# infinity_mirror_v0_9_0.net
KiCad netlist of a schematic drawn in EAGLE
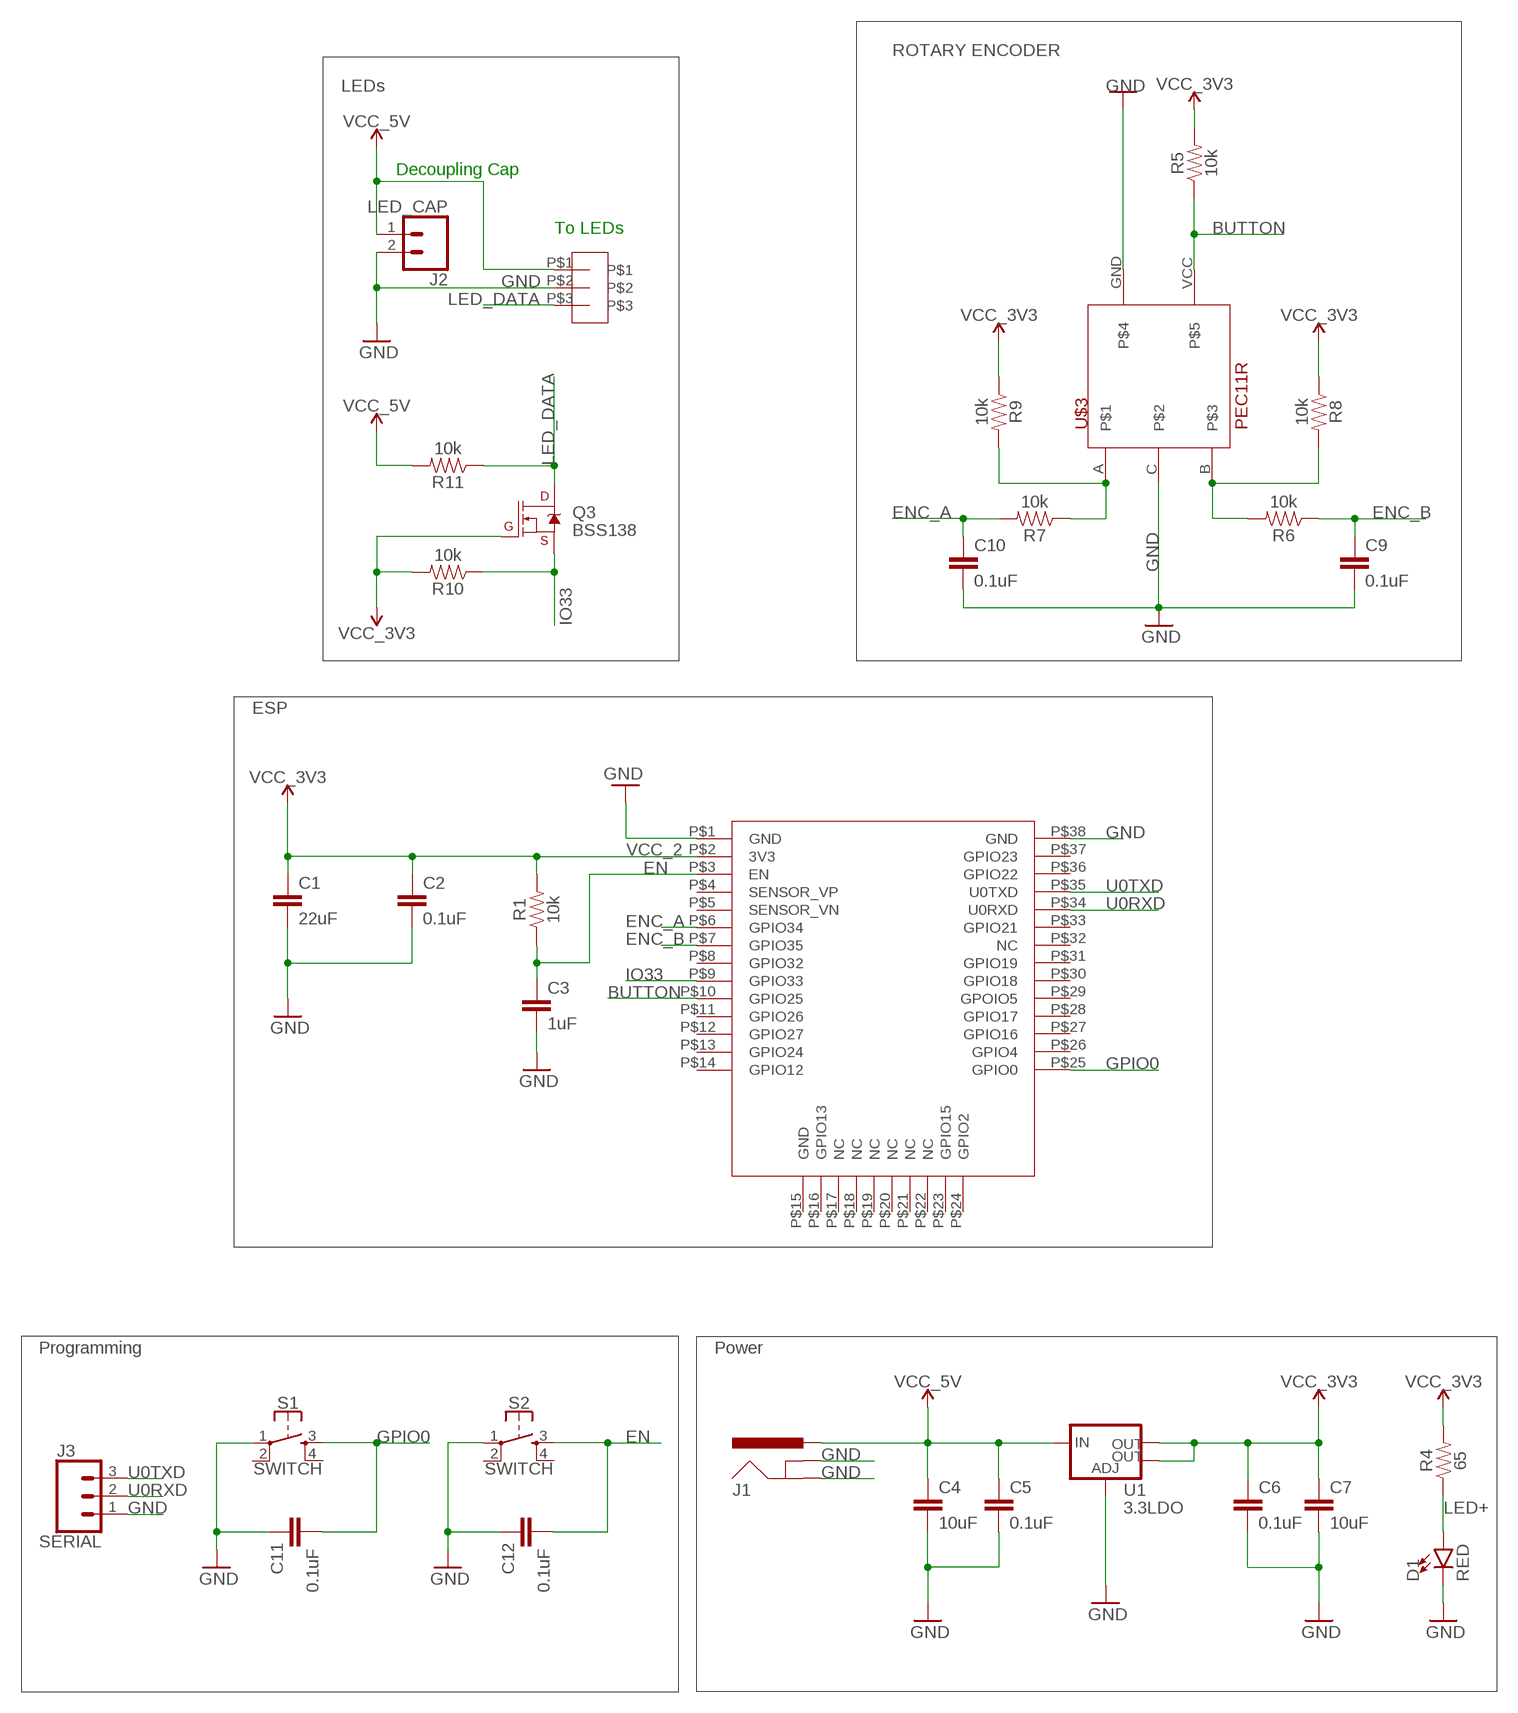
[diagram p0: schematic, sheet 1]

(export (version "E")
  (design (tool "Eeschema 10.0.6"))
  (components
    (comp (ref "C1")
      (value "22uF")
      (footprint "eagle-import:0805")
      (libsource (lib "eagle-import") (part "CAPACITOR"))
    )
    (comp (ref "C2")
      (value "0.1uF")
      (footprint "eagle-import:0805")
      (libsource (lib "eagle-import") (part "CAPACITOR"))
    )
    (comp (ref "C3")
      (value "1uF")
      (footprint "eagle-import:0805")
      (libsource (lib "eagle-import") (part "CAPACITOR"))
    )
    (comp (ref "C4")
      (value "10uF")
      (footprint "eagle-import:0805")
      (libsource (lib "eagle-import") (part "CAPACITOR"))
    )
    (comp (ref "C5")
      (value "0.1uF")
      (footprint "eagle-import:0805")
      (libsource (lib "eagle-import") (part "CAPACITOR"))
    )
    (comp (ref "C6")
      (value "0.1uF")
      (footprint "eagle-import:0805")
      (libsource (lib "eagle-import") (part "CAPACITOR"))
    )
    (comp (ref "C7")
      (value "10uF")
      (footprint "eagle-import:0805")
      (libsource (lib "eagle-import") (part "CAPACITOR"))
    )
    (comp (ref "C9")
      (value "0.1uF")
      (footprint "eagle-import:0805")
      (libsource (lib "eagle-import") (part "CAPACITOR"))
    )
    (comp (ref "C10")
      (value "0.1uF")
      (footprint "eagle-import:0805")
      (libsource (lib "eagle-import") (part "CAPACITOR"))
    )
    (comp (ref "C11")
      (value "0.1uF")
      (footprint "eagle-import:0805")
      (libsource (lib "eagle-import") (part "CAPACITOR"))
    )
    (comp (ref "C12")
      (value "0.1uF")
      (footprint "eagle-import:0805")
      (libsource (lib "eagle-import") (part "CAPACITOR"))
    )
    (comp (ref "D1")
      (value "RED")
      (footprint "eagle-import:LED-1206")
      (libsource (lib "eagle-import") (part "LED-RED1206"))
    )
    (comp (ref "J1")
      (value "POWER_JACKPTH_BREAD")
      (footprint "eagle-import:POWER_JACK_PTH_BREAD")
      (libsource (lib "eagle-import") (part "POWER_JACKPTH_BREAD"))
    )
    (comp (ref "J2")
      (value "LED_CAP")
      (footprint "eagle-import:1X02")
      (libsource (lib "eagle-import") (part "CONN_02"))
    )
    (comp (ref "J3")
      (value "SERIAL")
      (footprint "eagle-import:1X03")
      (libsource (lib "eagle-import") (part "CONN_03"))
    )
    (comp (ref "Q3")
      (value "BSS138")
      (footprint "eagle-import:SOT23-3")
      (libsource (lib "eagle-import") (part "MOSFET-NCH-BSS138"))
    )
    (comp (ref "R1")
      (value "10k")
      (footprint "eagle-import:0805")
      (libsource (lib "eagle-import") (part "RESISTOR"))
    )
    (comp (ref "R4")
      (value "65")
      (footprint "eagle-import:0805")
      (libsource (lib "eagle-import") (part "RESISTOR"))
    )
    (comp (ref "R5")
      (value "10k")
      (footprint "eagle-import:0805")
      (libsource (lib "eagle-import") (part "RESISTOR"))
    )
    (comp (ref "R6")
      (value "10k")
      (footprint "eagle-import:0805")
      (libsource (lib "eagle-import") (part "RESISTOR"))
    )
    (comp (ref "R7")
      (value "10k")
      (footprint "eagle-import:0805")
      (libsource (lib "eagle-import") (part "RESISTOR"))
    )
    (comp (ref "R8")
      (value "10k")
      (footprint "eagle-import:0805")
      (libsource (lib "eagle-import") (part "RESISTOR"))
    )
    (comp (ref "R9")
      (value "10k")
      (footprint "eagle-import:0805")
      (libsource (lib "eagle-import") (part "RESISTOR"))
    )
    (comp (ref "R10")
      (value "10k")
      (footprint "eagle-import:0805")
      (libsource (lib "eagle-import") (part "RESISTOR"))
    )
    (comp (ref "R11")
      (value "10k")
      (footprint "eagle-import:0805")
      (libsource (lib "eagle-import") (part "RESISTOR"))
    )
    (comp (ref "S1")
      (value "SWITCH")
      (footprint "eagle-import:TACTILE_SWITCH_SMD_5.2MM")
      (libsource (lib "eagle-import") (part "MOMENTARY-SWITCH-SPST-2-SMD-5.2MM-TALL"))
    )
    (comp (ref "S2")
      (value "SWITCH")
      (footprint "eagle-import:TACTILE_SWITCH_SMD_5.2MM")
      (libsource (lib "eagle-import") (part "MOMENTARY-SWITCH-SPST-2-SMD-5.2MM-TALL"))
    )
    (comp (ref "U$1")
      (value "ESP32-WROOM-32E")
      (footprint "eagle-import:ESP32-WROOM-32E")
      (libsource (lib "eagle-import") (part "ESP32-WROOM-32E"))
    )
    (comp (ref "U$2")
      (value "3-PIN-JST")
      (footprint "eagle-import:3-PIN-JST")
      (libsource (lib "eagle-import") (part "3-PIN-JST"))
    )
    (comp (ref "U$3")
      (value "PEC11R")
      (footprint "eagle-import:PEC11R-4320F-S0012")
      (libsource (lib "eagle-import") (part "PEC11R_ROTARY_ENCODER"))
    )
    (comp (ref "U1")
      (value "3.3LDO")
      (footprint "eagle-import:SOT223")
      (libsource (lib "eagle-import") (part "V_REG_LM1117SOT223"))
    )
  )
  (nets
    (net (code "1") (name "/BUTTON") (class "Default")
      (node (ref "R5") (pin "1") (pinfunction "1_1") (pintype "passive"))
      (node (ref "U$1") (pin "P$10") (pinfunction "GPIO25_P$10") (pintype "bidirectional"))
      (node (ref "U$3") (pin "VCC") (pinfunction "P$5_VCC") (pintype "bidirectional"))
    )
    (net (code "2") (name "/EN") (class "Default")
      (node (ref "C12") (pin "2") (pinfunction "2_2") (pintype "passive"))
      (node (ref "C3") (pin "1") (pinfunction "1_1") (pintype "passive"))
      (node (ref "R1") (pin "1") (pinfunction "1_1") (pintype "passive"))
      (node (ref "S2") (pin "3") (pinfunction "3_3") (pintype "passive"))
      (node (ref "U$1") (pin "P$3") (pinfunction "EN_P$3") (pintype "bidirectional"))
    )
    (net (code "3") (name "/ENC_A") (class "Default")
      (node (ref "C10") (pin "1") (pinfunction "1_1") (pintype "passive"))
      (node (ref "R7") (pin "2") (pinfunction "2_2") (pintype "passive"))
      (node (ref "U$1") (pin "P$6") (pinfunction "GPIO34_P$6") (pintype "bidirectional"))
    )
    (net (code "4") (name "/ENC_B") (class "Default")
      (node (ref "C9") (pin "1") (pinfunction "1_1") (pintype "passive"))
      (node (ref "R6") (pin "1") (pinfunction "1_1") (pintype "passive"))
      (node (ref "U$1") (pin "P$7") (pinfunction "GPIO35_P$7") (pintype "bidirectional"))
    )
    (net (code "5") (name "/GPIO0") (class "Default")
      (node (ref "C11") (pin "2") (pinfunction "2_2") (pintype "passive"))
      (node (ref "S1") (pin "3") (pinfunction "3_3") (pintype "passive"))
      (node (ref "U$1") (pin "P$25") (pinfunction "GPIO0_P$25") (pintype "bidirectional"))
    )
    (net (code "6") (name "/IO33") (class "Default")
      (node (ref "Q3") (pin "2") (pinfunction "S_2") (pintype "bidirectional"))
      (node (ref "R10") (pin "1") (pinfunction "1_1") (pintype "passive"))
      (node (ref "U$1") (pin "P$9") (pinfunction "GPIO33_P$9") (pintype "bidirectional"))
    )
    (net (code "7") (name "/LED+") (class "Default")
      (node (ref "D1") (pin "A") (pinfunction "A_A") (pintype "passive"))
      (node (ref "R4") (pin "1") (pinfunction "1_1") (pintype "passive"))
    )
    (net (code "8") (name "/LED_DATA") (class "Default")
      (node (ref "Q3") (pin "3") (pinfunction "D_3") (pintype "bidirectional"))
      (node (ref "R11") (pin "1") (pinfunction "1_1") (pintype "passive"))
      (node (ref "U$2") (pin "P$3") (pinfunction "P$3_P$3") (pintype "bidirectional"))
    )
    (net (code "9") (name "/U0RXD") (class "Default")
      (node (ref "J3") (pin "2") (pinfunction "2_2") (pintype "passive"))
      (node (ref "U$1") (pin "P$34") (pinfunction "U0RXD_P$34") (pintype "bidirectional"))
    )
    (net (code "10") (name "/U0TXD") (class "Default")
      (node (ref "J3") (pin "3") (pinfunction "3_3") (pintype "passive"))
      (node (ref "U$1") (pin "P$35") (pinfunction "U0TXD_P$35") (pintype "bidirectional"))
    )
    (net (code "11") (name "GND") (class "Default")
      (node (ref "C1") (pin "2") (pinfunction "2_2") (pintype "passive"))
      (node (ref "C10") (pin "2") (pinfunction "2_2") (pintype "passive"))
      (node (ref "C11") (pin "1") (pinfunction "1_1") (pintype "passive"))
      (node (ref "C12") (pin "1") (pinfunction "1_1") (pintype "passive"))
      (node (ref "C2") (pin "2") (pinfunction "2_2") (pintype "passive"))
      (node (ref "C3") (pin "2") (pinfunction "2_2") (pintype "passive"))
      (node (ref "C4") (pin "2") (pinfunction "2_2") (pintype "passive"))
      (node (ref "C5") (pin "2") (pinfunction "2_2") (pintype "passive"))
      (node (ref "C6") (pin "2") (pinfunction "2_2") (pintype "passive"))
      (node (ref "C7") (pin "2") (pinfunction "2_2") (pintype "passive"))
      (node (ref "C9") (pin "2") (pinfunction "2_2") (pintype "passive"))
      (node (ref "D1") (pin "C") (pinfunction "C_C") (pintype "passive"))
      (node (ref "J1") (pin "GND") (pinfunction "GND_GND") (pintype "bidirectional"))
      (node (ref "J1") (pin "GNDBREAK") (pinfunction "GNDBREAK_GNDBREAK") (pintype "bidirectional"))
      (node (ref "J2") (pin "2") (pinfunction "2_2") (pintype "passive"))
      (node (ref "J3") (pin "1") (pinfunction "1_1") (pintype "passive"))
      (node (ref "S1") (pin "1") (pinfunction "1_1") (pintype "passive"))
      (node (ref "S2") (pin "1") (pinfunction "1_1") (pintype "passive"))
      (node (ref "U$1") (pin "P$1") (pinfunction "GND_P$1") (pintype "bidirectional"))
      (node (ref "U$1") (pin "P$38") (pinfunction "GND_P$38") (pintype "bidirectional"))
      (node (ref "U$2") (pin "P$2") (pinfunction "P$2_P$2") (pintype "bidirectional"))
      (node (ref "U$3") (pin "C") (pinfunction "P$2_C") (pintype "bidirectional"))
      (node (ref "U$3") (pin "GND") (pinfunction "P$4_GND") (pintype "bidirectional"))
      (node (ref "U1") (pin "1") (pinfunction "ADJ_1") (pintype "input"))
    )
    (net (code "12") (name "Net-(U$3-P$1)") (class "Default")
      (node (ref "R7") (pin "1") (pinfunction "1_1") (pintype "passive"))
      (node (ref "R9") (pin "2") (pinfunction "2_2") (pintype "passive"))
      (node (ref "U$3") (pin "A") (pinfunction "P$1_A") (pintype "bidirectional"))
    )
    (net (code "13") (name "Net-(U$3-P$3)") (class "Default")
      (node (ref "R6") (pin "2") (pinfunction "2_2") (pintype "passive"))
      (node (ref "R8") (pin "2") (pinfunction "2_2") (pintype "passive"))
      (node (ref "U$3") (pin "B") (pinfunction "P$3_B") (pintype "bidirectional"))
    )
    (net (code "14") (name "VCC_3V3") (class "Default")
      (node (ref "C1") (pin "1") (pinfunction "1_1") (pintype "passive"))
      (node (ref "C2") (pin "1") (pinfunction "1_1") (pintype "passive"))
      (node (ref "C6") (pin "1") (pinfunction "1_1") (pintype "passive"))
      (node (ref "C7") (pin "1") (pinfunction "1_1") (pintype "passive"))
      (node (ref "Q3") (pin "1") (pinfunction "G_1") (pintype "bidirectional"))
      (node (ref "R1") (pin "2") (pinfunction "2_2") (pintype "passive"))
      (node (ref "R10") (pin "2") (pinfunction "2_2") (pintype "passive"))
      (node (ref "R4") (pin "2") (pinfunction "2_2") (pintype "passive"))
      (node (ref "R5") (pin "2") (pinfunction "2_2") (pintype "passive"))
      (node (ref "R8") (pin "1") (pinfunction "1_1") (pintype "passive"))
      (node (ref "R9") (pin "1") (pinfunction "1_1") (pintype "passive"))
      (node (ref "U$1") (pin "P$2") (pinfunction "3V3_P$2") (pintype "bidirectional"))
      (node (ref "U1") (pin "2") (pinfunction "OUT_2") (pintype "output"))
      (node (ref "U1") (pin "4") (pinfunction "OUT_4") (pintype "output"))
    )
    (net (code "15") (name "VCC_5V") (class "Default")
      (node (ref "C4") (pin "1") (pinfunction "1_1") (pintype "passive"))
      (node (ref "C5") (pin "1") (pinfunction "1_1") (pintype "passive"))
      (node (ref "J1") (pin "PWR") (pinfunction "PWR_PWR") (pintype "bidirectional"))
      (node (ref "J2") (pin "1") (pinfunction "1_1") (pintype "passive"))
      (node (ref "R11") (pin "2") (pinfunction "2_2") (pintype "passive"))
      (node (ref "U$2") (pin "P$1") (pinfunction "P$1_P$1") (pintype "bidirectional"))
      (node (ref "U1") (pin "3") (pinfunction "IN_3") (pintype "input"))
    )
    (net (code "16") (name "unconnected-(S1-Pad2)") (class "Default")
      (node (ref "S1") (pin "2") (pinfunction "2_2") (pintype "passive"))
    )
    (net (code "17") (name "unconnected-(S1-Pad4)") (class "Default")
      (node (ref "S1") (pin "4") (pinfunction "4_4") (pintype "passive"))
    )
    (net (code "18") (name "unconnected-(S2-Pad2)") (class "Default")
      (node (ref "S2") (pin "2") (pinfunction "2_2") (pintype "passive"))
    )
    (net (code "19") (name "unconnected-(S2-Pad4)") (class "Default")
      (node (ref "S2") (pin "4") (pinfunction "4_4") (pintype "passive"))
    )
    (net (code "20") (name "unconnected-(U$1-GND-PadP$15)") (class "Default")
      (node (ref "U$1") (pin "P$15") (pinfunction "GND_P$15") (pintype "bidirectional"))
    )
    (net (code "21") (name "unconnected-(U$1-GPIO2-PadP$24)") (class "Default")
      (node (ref "U$1") (pin "P$24") (pinfunction "GPIO2_P$24") (pintype "bidirectional"))
    )
    (net (code "22") (name "unconnected-(U$1-GPIO4-PadP$26)") (class "Default")
      (node (ref "U$1") (pin "P$26") (pinfunction "GPIO4_P$26") (pintype "bidirectional"))
    )
    (net (code "23") (name "unconnected-(U$1-GPIO12-PadP$14)") (class "Default")
      (node (ref "U$1") (pin "P$14") (pinfunction "GPIO12_P$14") (pintype "bidirectional"))
    )
    (net (code "24") (name "unconnected-(U$1-GPIO13-PadP$16)") (class "Default")
      (node (ref "U$1") (pin "P$16") (pinfunction "GPIO13_P$16") (pintype "bidirectional"))
    )
    (net (code "25") (name "unconnected-(U$1-GPIO15-PadP$23)") (class "Default")
      (node (ref "U$1") (pin "P$23") (pinfunction "GPIO15_P$23") (pintype "bidirectional"))
    )
    (net (code "26") (name "unconnected-(U$1-GPIO16-PadP$27)") (class "Default")
      (node (ref "U$1") (pin "P$27") (pinfunction "GPIO16_P$27") (pintype "bidirectional"))
    )
    (net (code "27") (name "unconnected-(U$1-GPIO17-PadP$28)") (class "Default")
      (node (ref "U$1") (pin "P$28") (pinfunction "GPIO17_P$28") (pintype "bidirectional"))
    )
    (net (code "28") (name "unconnected-(U$1-GPIO18-PadP$30)") (class "Default")
      (node (ref "U$1") (pin "P$30") (pinfunction "GPIO18_P$30") (pintype "bidirectional"))
    )
    (net (code "29") (name "unconnected-(U$1-GPIO19-PadP$31)") (class "Default")
      (node (ref "U$1") (pin "P$31") (pinfunction "GPIO19_P$31") (pintype "bidirectional"))
    )
    (net (code "30") (name "unconnected-(U$1-GPIO21-PadP$33)") (class "Default")
      (node (ref "U$1") (pin "P$33") (pinfunction "GPIO21_P$33") (pintype "bidirectional"))
    )
    (net (code "31") (name "unconnected-(U$1-GPIO22-PadP$36)") (class "Default")
      (node (ref "U$1") (pin "P$36") (pinfunction "GPIO22_P$36") (pintype "bidirectional"))
    )
    (net (code "32") (name "unconnected-(U$1-GPIO23-PadP$37)") (class "Default")
      (node (ref "U$1") (pin "P$37") (pinfunction "GPIO23_P$37") (pintype "bidirectional"))
    )
    (net (code "33") (name "unconnected-(U$1-GPIO24-PadP$13)") (class "Default")
      (node (ref "U$1") (pin "P$13") (pinfunction "GPIO24_P$13") (pintype "bidirectional"))
    )
    (net (code "34") (name "unconnected-(U$1-GPIO26-PadP$11)") (class "Default")
      (node (ref "U$1") (pin "P$11") (pinfunction "GPIO26_P$11") (pintype "bidirectional"))
    )
    (net (code "35") (name "unconnected-(U$1-GPIO27-PadP$12)") (class "Default")
      (node (ref "U$1") (pin "P$12") (pinfunction "GPIO27_P$12") (pintype "bidirectional"))
    )
    (net (code "36") (name "unconnected-(U$1-GPIO32-PadP$8)") (class "Default")
      (node (ref "U$1") (pin "P$8") (pinfunction "GPIO32_P$8") (pintype "bidirectional"))
    )
    (net (code "37") (name "unconnected-(U$1-GPOIO5-PadP$29)") (class "Default")
      (node (ref "U$1") (pin "P$29") (pinfunction "GPOIO5_P$29") (pintype "bidirectional"))
    )
    (net (code "38") (name "unconnected-(U$1-NC-PadP$17)") (class "Default")
      (node (ref "U$1") (pin "P$17") (pinfunction "NC_P$17") (pintype "bidirectional"))
    )
    (net (code "39") (name "unconnected-(U$1-NC-PadP$18)") (class "Default")
      (node (ref "U$1") (pin "P$18") (pinfunction "NC_P$18") (pintype "bidirectional"))
    )
    (net (code "40") (name "unconnected-(U$1-NC-PadP$19)") (class "Default")
      (node (ref "U$1") (pin "P$19") (pinfunction "NC_P$19") (pintype "bidirectional"))
    )
    (net (code "41") (name "unconnected-(U$1-NC-PadP$20)") (class "Default")
      (node (ref "U$1") (pin "P$20") (pinfunction "NC_P$20") (pintype "bidirectional"))
    )
    (net (code "42") (name "unconnected-(U$1-NC-PadP$21)") (class "Default")
      (node (ref "U$1") (pin "P$21") (pinfunction "NC_P$21") (pintype "bidirectional"))
    )
    (net (code "43") (name "unconnected-(U$1-NC-PadP$22)") (class "Default")
      (node (ref "U$1") (pin "P$22") (pinfunction "NC_P$22") (pintype "bidirectional"))
    )
    (net (code "44") (name "unconnected-(U$1-NC-PadP$32)") (class "Default")
      (node (ref "U$1") (pin "P$32") (pinfunction "NC_P$32") (pintype "bidirectional"))
    )
    (net (code "45") (name "unconnected-(U$1-SENSOR_VN-PadP$5)") (class "Default")
      (node (ref "U$1") (pin "P$5") (pinfunction "SENSOR_VN_P$5") (pintype "bidirectional"))
    )
    (net (code "46") (name "unconnected-(U$1-SENSOR_VP-PadP$4)") (class "Default")
      (node (ref "U$1") (pin "P$4") (pinfunction "SENSOR_VP_P$4") (pintype "bidirectional"))
    )
  )
)
